# DCDC.net
KiCad netlist of a schematic drawn in Altium Designer
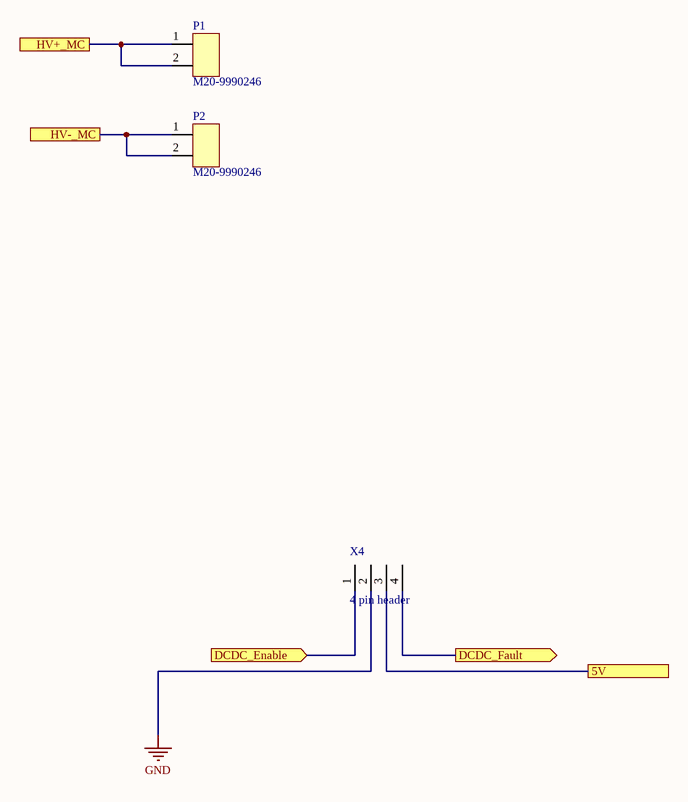
[diagram p0: DCDC.SchDoc]

(export (version "E")
  (design (tool "Eeschema 10.0.6"))
  (components
    (comp (ref "P1")
      (value "M20-9990246")
      (footprint "M20-9990246")
      (description "2 Pin VCC Power Header, Male")
      (fields (field (name "CREATED_BY") "Austin") (field (name "UPDATED_BY") "Null"))
      (libsource (lib "Altium-Lib") (part "M20-9990246"))
    )
    (comp (ref "P2")
      (value "M20-9990246")
      (footprint "M20-9990246")
      (description "2 Pin VCC Power Header, Male")
      (fields (field (name "CREATED_BY") "Austin") (field (name "UPDATED_BY") "Null"))
      (libsource (lib "Altium-Lib") (part "M20-9990246"))
    )
    (comp (ref "X4")
      (value "4 pin header")
      (footprint "4pinheader")
      (libsource (lib "altlib") (part "4pinheader"))
    )
  )
  (nets
    (net (code "1") (name "/5V") (class "Default") (node (ref "X4") (pin "3") (pintype "passive")))
    (net (code "2") (name "/DCDC_Enable") (class "Default") (node (ref "X4") (pin "1") (pintype "passive")))
    (net (code "3") (name "/DCDC_Fault") (class "Default") (node (ref "X4") (pin "4") (pintype "passive")))
    (net (code "4") (name "/HV+_MC") (class "Default")
      (node (ref "P1") (pin "1") (pintype "passive"))
      (node (ref "P1") (pin "2") (pintype "passive"))
    )
    (net (code "5") (name "/HV-_MC") (class "Default")
      (node (ref "P2") (pin "1") (pintype "passive"))
      (node (ref "P2") (pin "2") (pintype "passive"))
    )
    (net (code "6") (name "GND") (class "Default") (node (ref "X4") (pin "2") (pintype "passive")))
  )
)
